# stm32f072.net
KiCad netlist of a schematic drawn in EAGLE
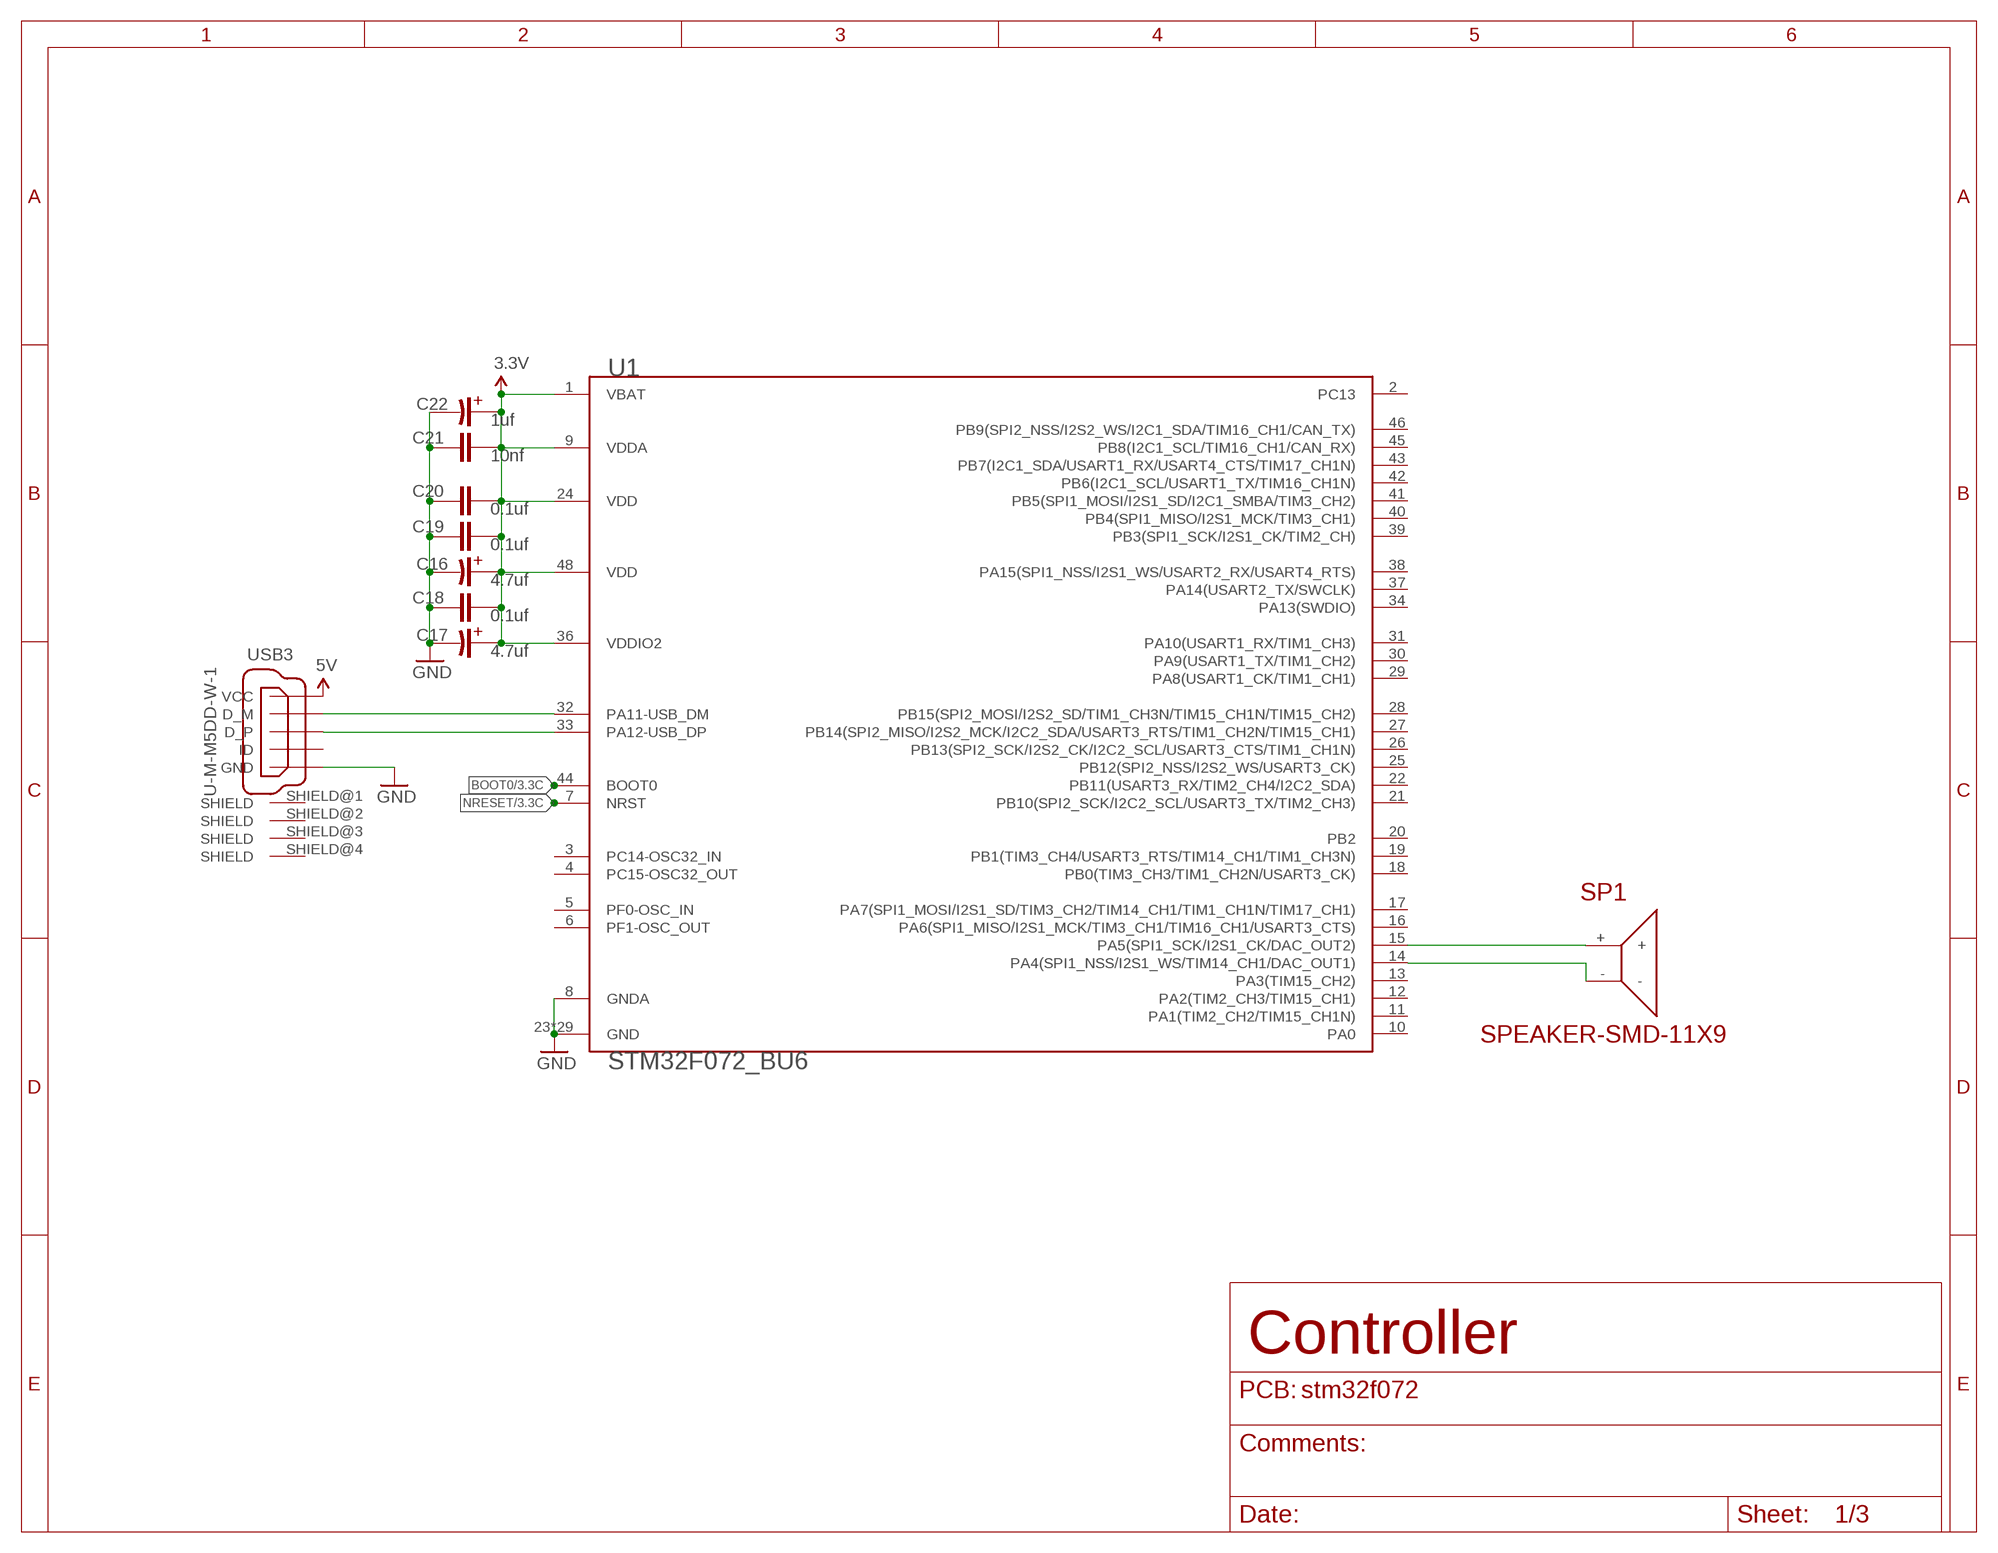
[diagram p0: schematic, sheet 1]
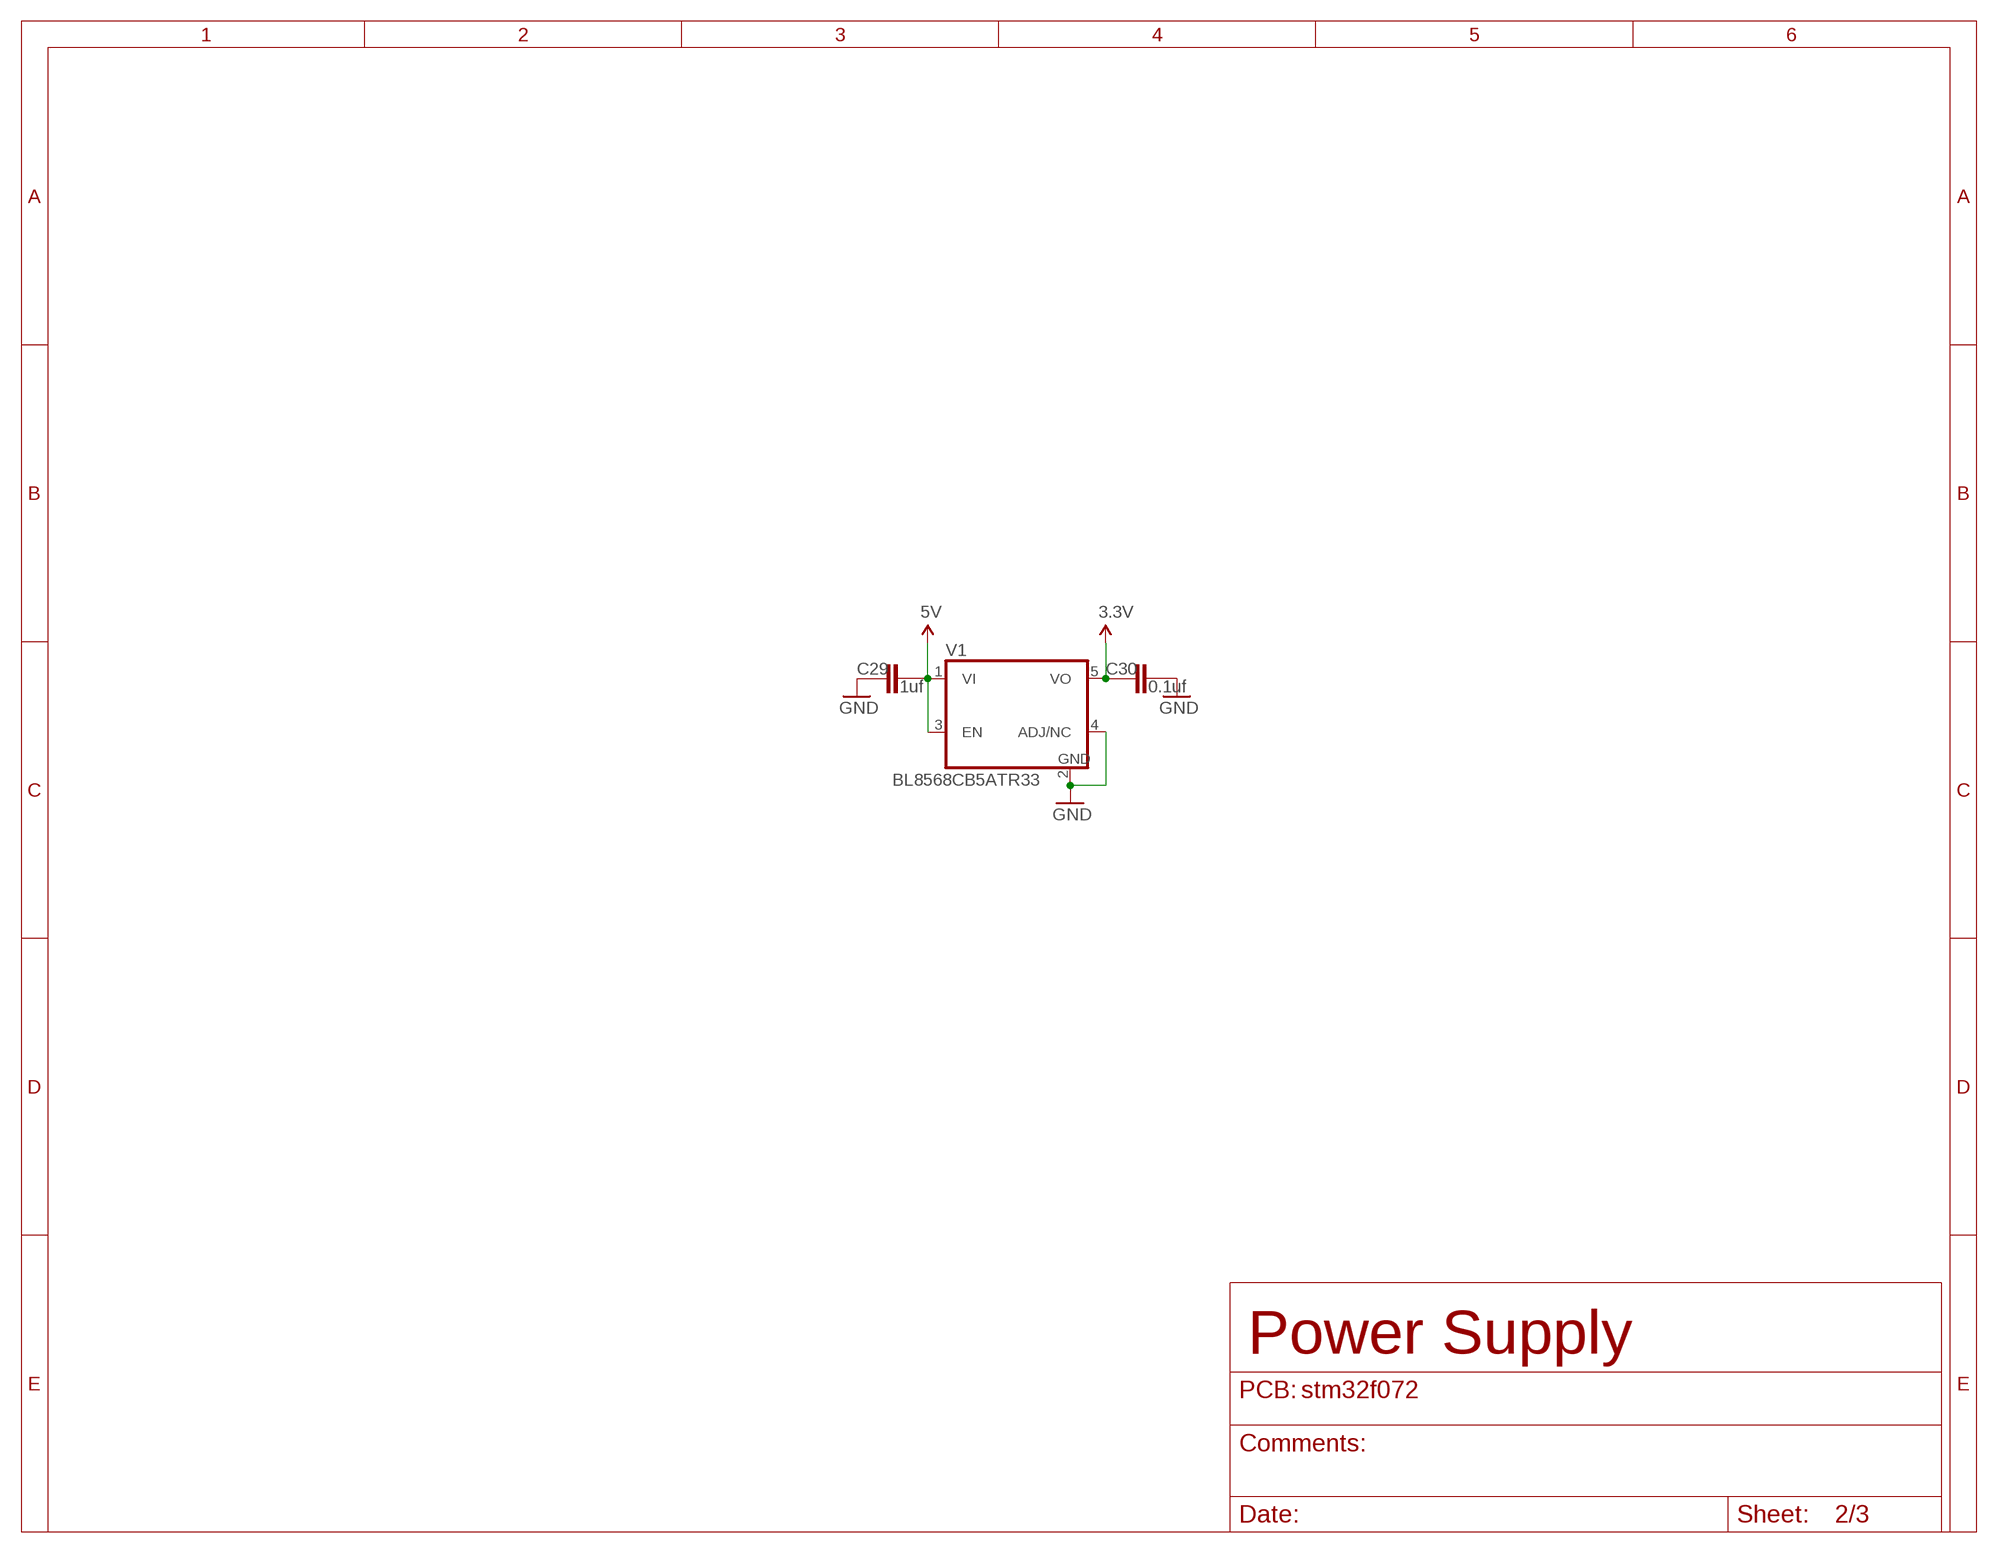
[diagram p1: schematic, sheet 2]
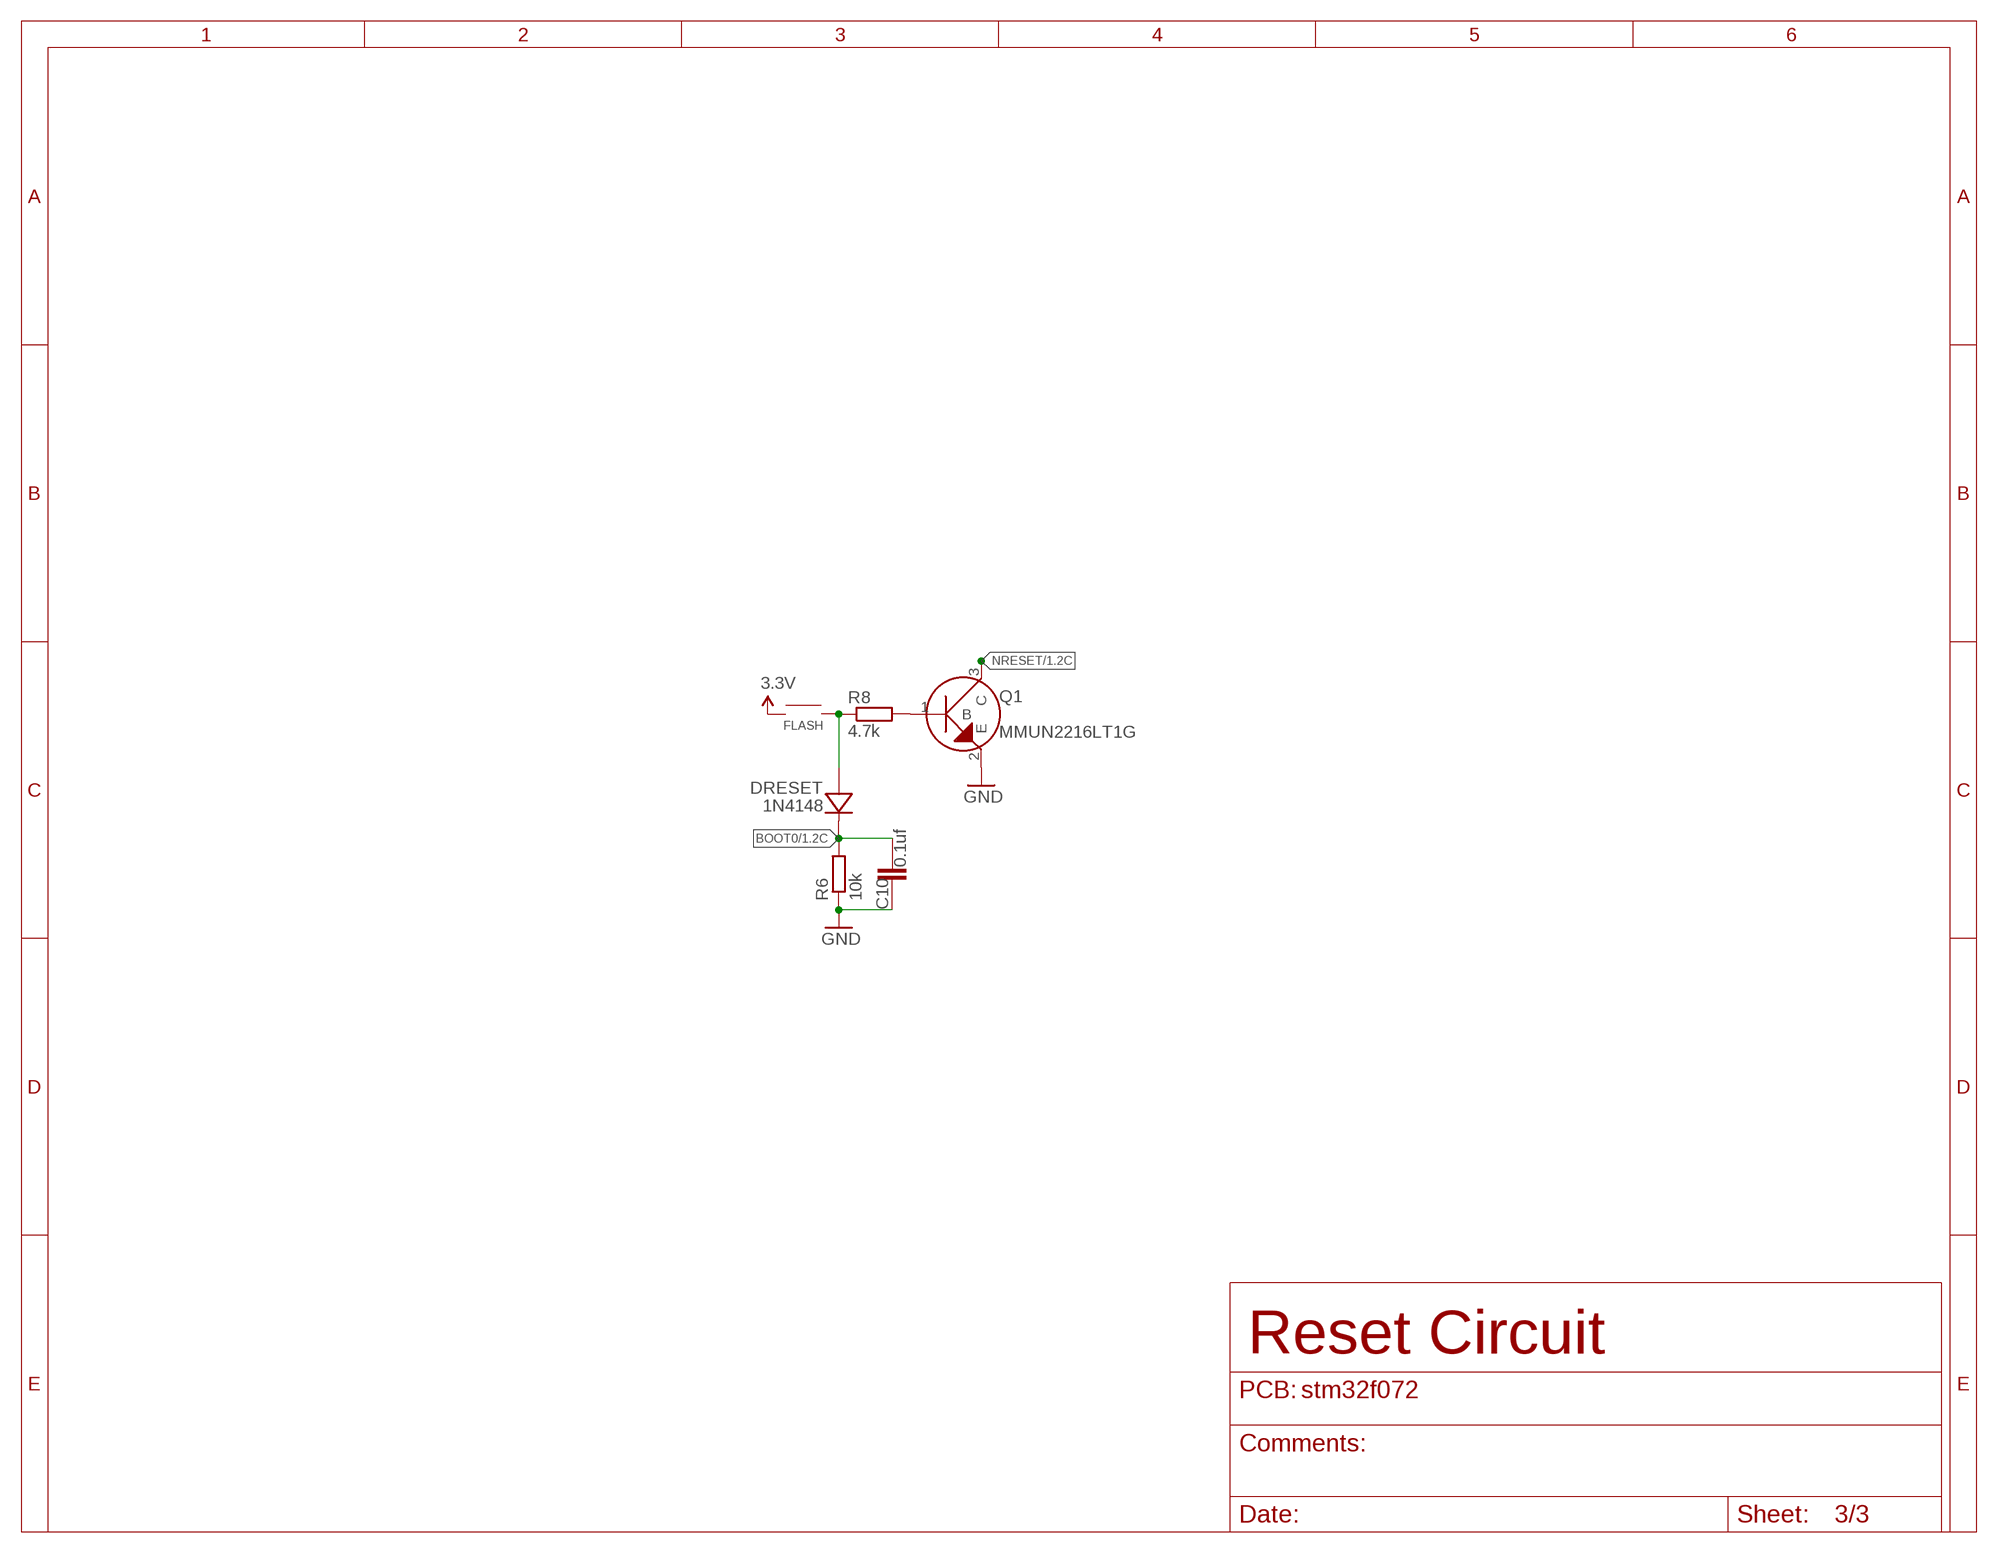
[diagram p2: schematic, sheet 3]

(export (version "E")
  (design (tool "Eeschema 10.0.6"))
  (components
    (comp (ref "C16")
      (value "4.7uf")
      (footprint "eagle-import:C0805-TANT")
      (libsource (lib "eagle-import") (part "CAPACITOR-TANT-0805"))
    )
    (comp (ref "C17")
      (value "4.7uf")
      (footprint "eagle-import:C0805-TANT")
      (libsource (lib "eagle-import") (part "CAPACITOR-TANT-0805"))
    )
    (comp (ref "C18")
      (value "0.1uf")
      (footprint "eagle-import:C0402")
      (libsource (lib "eagle-import") (part "CAPACITOR-0402"))
    )
    (comp (ref "C19")
      (value "0.1uf")
      (footprint "eagle-import:C0402")
      (libsource (lib "eagle-import") (part "CAPACITOR-0402"))
    )
    (comp (ref "C20")
      (value "0.1uf")
      (footprint "eagle-import:C0402")
      (libsource (lib "eagle-import") (part "CAPACITOR-0402"))
    )
    (comp (ref "C21")
      (value "10nf")
      (footprint "eagle-import:C0402")
      (libsource (lib "eagle-import") (part "CAPACITOR-0402"))
    )
    (comp (ref "C22")
      (value "1uf")
      (footprint "eagle-import:C0805-TANT")
      (libsource (lib "eagle-import") (part "CAPACITOR-TANT-0805"))
    )
    (comp (ref "SP1")
      (value "SPEAKER-SMD-11X9")
      (footprint "eagle-import:AST1109MLTRQ")
      (libsource (lib "eagle-import") (part "SPEAKER-SMD-11X9"))
    )
    (comp (ref "U1")
      (value "STM32F072_BU6")
      (footprint "eagle-import:UFQFPN-48")
      (libsource (lib "eagle-import") (part "STM32F072_BU6"))
    )
    (comp (ref "USB3")
      (value "U-M-M5DD-W-1")
      (footprint "eagle-import:U-M-M5DD-W-1")
      (libsource (lib "eagle-import") (part "USB_CONN-LCSC"))
    )
    (comp (ref "C29")
      (value "1uf")
      (footprint "eagle-import:C0402")
      (libsource (lib "eagle-import") (part "CAPACITOR-0402"))
    )
    (comp (ref "C30")
      (value "0.1uf")
      (footprint "eagle-import:C0402")
      (libsource (lib "eagle-import") (part "CAPACITOR-0402"))
    )
    (comp (ref "V1")
      (value "BL8568CB5ATR33")
      (footprint "eagle-import:SOT-23-5")
      (libsource (lib "eagle-import") (part "LDO-VR"))
    )
    (comp (ref "C10")
      (value "0.1uf")
      (footprint "eagle-import:C0402")
      (libsource (lib "eagle-import") (part "CAPACITOR-0402"))
    )
    (comp (ref "DRESET")
      (value "1N4148")
      (footprint "eagle-import:SOD-123")
      (libsource (lib "eagle-import") (part "DIODE-SOD-123"))
    )
    (comp (ref "FLASH")
      (value "SKRPABE010")
      (footprint "eagle-import:SWITCH-SMD-SKRPABE010")
      (libsource (lib "eagle-import") (part "SWITCH-SMD-SKRPABE010"))
    )
    (comp (ref "Q1")
      (value "MMUN2216LT1G")
      (footprint "eagle-import:SOT-23-3")
      (libsource (lib "eagle-import") (part "TRANSISTOR-NPN"))
    )
    (comp (ref "R6")
      (value "10k")
      (footprint "eagle-import:R0402")
      (libsource (lib "eagle-import") (part "RESISTOR-0405"))
    )
    (comp (ref "R8")
      (value "4.7k")
      (footprint "eagle-import:R0402")
      (libsource (lib "eagle-import") (part "RESISTOR-0405"))
    )
  )
  (nets
    (net (code "1") (name "3.3V") (class "Default")
      (node (ref "C16") (pin "1") (pinfunction "+_1") (pintype "passive"))
      (node (ref "C17") (pin "1") (pinfunction "+_1") (pintype "passive"))
      (node (ref "C18") (pin "2") (pinfunction "2_2") (pintype "passive"))
      (node (ref "C19") (pin "2") (pinfunction "2_2") (pintype "passive"))
      (node (ref "C20") (pin "2") (pinfunction "2_2") (pintype "passive"))
      (node (ref "C21") (pin "2") (pinfunction "2_2") (pintype "passive"))
      (node (ref "C22") (pin "1") (pinfunction "+_1") (pintype "passive"))
      (node (ref "C30") (pin "1") (pinfunction "1_1") (pintype "passive"))
      (node (ref "FLASH") (pin "1A") (pinfunction "1_1A") (pintype "passive"))
      (node (ref "FLASH") (pin "1B") (pinfunction "1_1B") (pintype "passive"))
      (node (ref "U1") (pin "1") (pinfunction "VBAT_1") (pintype "bidirectional"))
      (node (ref "U1") (pin "24") (pinfunction "VDD_24") (pintype "bidirectional"))
      (node (ref "U1") (pin "36") (pinfunction "VDDIO2_36") (pintype "bidirectional"))
      (node (ref "U1") (pin "48") (pinfunction "VDD_48") (pintype "bidirectional"))
      (node (ref "U1") (pin "9") (pinfunction "VDDA_9") (pintype "bidirectional"))
      (node (ref "V1") (pin "5") (pinfunction "VO_5") (pintype "passive"))
    )
    (net (code "2") (name "5V") (class "Default")
      (node (ref "C29") (pin "2") (pinfunction "2_2") (pintype "passive"))
      (node (ref "USB3") (pin "VCC") (pinfunction "VCC_VCC") (pintype "input"))
      (node (ref "V1") (pin "1") (pinfunction "VI_1") (pintype "input"))
      (node (ref "V1") (pin "3") (pinfunction "EN_3") (pintype "input"))
    )
    (net (code "3") (name "BOOT0") (class "Default")
      (node (ref "C10") (pin "2") (pinfunction "2_2") (pintype "passive"))
      (node (ref "DRESET") (pin "C") (pinfunction "C_C") (pintype "passive"))
      (node (ref "R6") (pin "2") (pinfunction "2_2") (pintype "passive"))
      (node (ref "U1") (pin "44") (pinfunction "BOOT0_44") (pintype "bidirectional"))
    )
    (net (code "4") (name "GND") (class "Default")
      (node (ref "C10") (pin "1") (pinfunction "1_1") (pintype "passive"))
      (node (ref "C16") (pin "2") (pinfunction "-_2") (pintype "passive"))
      (node (ref "C17") (pin "2") (pinfunction "-_2") (pintype "passive"))
      (node (ref "C18") (pin "1") (pinfunction "1_1") (pintype "passive"))
      (node (ref "C19") (pin "1") (pinfunction "1_1") (pintype "passive"))
      (node (ref "C20") (pin "1") (pinfunction "1_1") (pintype "passive"))
      (node (ref "C21") (pin "1") (pinfunction "1_1") (pintype "passive"))
      (node (ref "C22") (pin "2") (pinfunction "-_2") (pintype "passive"))
      (node (ref "C29") (pin "1") (pinfunction "1_1") (pintype "passive"))
      (node (ref "C30") (pin "2") (pinfunction "2_2") (pintype "passive"))
      (node (ref "Q1") (pin "2") (pinfunction "E_2") (pintype "bidirectional"))
      (node (ref "R6") (pin "1") (pinfunction "1_1") (pintype "passive"))
      (node (ref "U1") (pin "23") (pinfunction "GND_23") (pintype "bidirectional"))
      (node (ref "U1") (pin "35") (pinfunction "GND_35") (pintype "bidirectional"))
      (node (ref "U1") (pin "47") (pinfunction "GND_47") (pintype "bidirectional"))
      (node (ref "U1") (pin "8") (pinfunction "GNDA_8") (pintype "bidirectional"))
      (node (ref "U1") (pin "P$1") (pinfunction "GND_P$1") (pintype "bidirectional"))
      (node (ref "U1") (pin "P$10") (pinfunction "GND_P$10") (pintype "bidirectional"))
      (node (ref "U1") (pin "P$11") (pinfunction "GND_P$11") (pintype "bidirectional"))
      (node (ref "U1") (pin "P$12") (pinfunction "GND_P$12") (pintype "bidirectional"))
      (node (ref "U1") (pin "P$13") (pinfunction "GND_P$13") (pintype "bidirectional"))
      (node (ref "U1") (pin "P$14") (pinfunction "GND_P$14") (pintype "bidirectional"))
      (node (ref "U1") (pin "P$15") (pinfunction "GND_P$15") (pintype "bidirectional"))
      (node (ref "U1") (pin "P$16") (pinfunction "GND_P$16") (pintype "bidirectional"))
      (node (ref "U1") (pin "P$17") (pinfunction "GND_P$17") (pintype "bidirectional"))
      (node (ref "U1") (pin "P$18") (pinfunction "GND_P$18") (pintype "bidirectional"))
      (node (ref "U1") (pin "P$19") (pinfunction "GND_P$19") (pintype "bidirectional"))
      (node (ref "U1") (pin "P$2") (pinfunction "GND_P$2") (pintype "bidirectional"))
      (node (ref "U1") (pin "P$20") (pinfunction "GND_P$20") (pintype "bidirectional"))
      (node (ref "U1") (pin "P$21") (pinfunction "GND_P$21") (pintype "bidirectional"))
      (node (ref "U1") (pin "P$22") (pinfunction "GND_P$22") (pintype "bidirectional"))
      (node (ref "U1") (pin "P$23") (pinfunction "GND_P$23") (pintype "bidirectional"))
      (node (ref "U1") (pin "P$24") (pinfunction "GND_P$24") (pintype "bidirectional"))
      (node (ref "U1") (pin "P$25") (pinfunction "GND_P$25") (pintype "bidirectional"))
      (node (ref "U1") (pin "P$3") (pinfunction "GND_P$3") (pintype "bidirectional"))
      (node (ref "U1") (pin "P$4") (pinfunction "GND_P$4") (pintype "bidirectional"))
      (node (ref "U1") (pin "P$5") (pinfunction "GND_P$5") (pintype "bidirectional"))
      (node (ref "U1") (pin "P$6") (pinfunction "GND_P$6") (pintype "bidirectional"))
      (node (ref "U1") (pin "P$7") (pinfunction "GND_P$7") (pintype "bidirectional"))
      (node (ref "U1") (pin "P$8") (pinfunction "GND_P$8") (pintype "bidirectional"))
      (node (ref "U1") (pin "P$9") (pinfunction "GND_P$9") (pintype "bidirectional"))
      (node (ref "U1") (pin "PAD") (pinfunction "GND_PAD") (pintype "bidirectional"))
      (node (ref "USB3") (pin "GND") (pinfunction "GND_GND") (pintype "input"))
      (node (ref "V1") (pin "2") (pinfunction "GND_2") (pintype "passive"))
      (node (ref "V1") (pin "4") (pinfunction "ADJ/NC_4") (pintype "passive"))
    )
    (net (code "5") (name "NRESET") (class "Default")
      (node (ref "Q1") (pin "3") (pinfunction "C_3") (pintype "bidirectional"))
      (node (ref "U1") (pin "7") (pinfunction "NRST_7") (pintype "bidirectional"))
    )
    (net (code "6") (name "Net-(DRESET-PadA)") (class "Default")
      (node (ref "DRESET") (pin "A") (pinfunction "A_A") (pintype "passive"))
      (node (ref "FLASH") (pin "2A") (pinfunction "2_2A") (pintype "passive"))
      (node (ref "FLASH") (pin "2B") (pinfunction "2_2B") (pintype "passive"))
      (node (ref "R8") (pin "1") (pinfunction "1_1") (pintype "passive"))
    )
    (net (code "7") (name "Net-(Q1-B)") (class "Default")
      (node (ref "Q1") (pin "1") (pinfunction "B_1") (pintype "bidirectional"))
      (node (ref "R8") (pin "2") (pinfunction "2_2") (pintype "passive"))
    )
    (net (code "8") (name "Net-(U1-PA4(SPI1_NSS{slash}I2S1_WS{slash}TIM14_CH1{slash}DAC_OUT1))") (class "Default")
      (node (ref "SP1") (pin "-") (pinfunction "-_-") (pintype "bidirectional"))
      (node (ref "U1") (pin "14") (pinfunction "PA4(SPI1_NSS/I2S1_WS/TIM14_CH1/DAC_OUT1)_14") (pintype "bidirectional"))
    )
    (net (code "9") (name "Net-(U1-PA5(SPI1_SCK{slash}I2S1_CK{slash}DAC_OUT2))") (class "Default")
      (node (ref "SP1") (pin "+") (pinfunction "+_+") (pintype "bidirectional"))
      (node (ref "U1") (pin "15") (pinfunction "PA5(SPI1_SCK/I2S1_CK/DAC_OUT2)_15") (pintype "bidirectional"))
    )
    (net (code "10") (name "Net-(U1-PA11-USB_DM)") (class "Default")
      (node (ref "U1") (pin "32") (pinfunction "PA11-USB_DM_32") (pintype "bidirectional"))
      (node (ref "USB3") (pin "D-") (pinfunction "D_M_D-") (pintype "input"))
    )
    (net (code "11") (name "Net-(U1-PA12-USB_DP)") (class "Default")
      (node (ref "U1") (pin "33") (pinfunction "PA12-USB_DP_33") (pintype "bidirectional"))
      (node (ref "USB3") (pin "D+") (pinfunction "D_P_D+") (pintype "input"))
    )
    (net (code "12") (name "unconnected-(U1-PA0-Pad10)") (class "Default")
      (node (ref "U1") (pin "10") (pinfunction "PA0_10") (pintype "bidirectional"))
    )
    (net (code "13") (name "unconnected-(U1-PA1(TIM2_CH2{slash}TIM15_CH1N)-Pad11)") (class "Default")
      (node (ref "U1") (pin "11") (pinfunction "PA1(TIM2_CH2/TIM15_CH1N)_11") (pintype "bidirectional"))
    )
    (net (code "14") (name "unconnected-(U1-PA2(TIM2_CH3{slash}TIM15_CH1)-Pad12)") (class "Default")
      (node (ref "U1") (pin "12") (pinfunction "PA2(TIM2_CH3/TIM15_CH1)_12") (pintype "bidirectional"))
    )
    (net (code "15") (name "unconnected-(U1-PA3(TIM15_CH2)-Pad13)") (class "Default")
      (node (ref "U1") (pin "13") (pinfunction "PA3(TIM15_CH2)_13") (pintype "bidirectional"))
    )
    (net (code "16") (name "unconnected-(U1-PA6(SPI1_MISO{slash}I2S1_MCK{slash}TIM3_CH1{slash}TIM16_CH1{slash}USART3_CTS)-Pad16)") (class "Default")
      (node (ref "U1") (pin "16") (pinfunction "PA6(SPI1_MISO/I2S1_MCK/TIM3_CH1/TIM16_CH1/USART3_CTS)_16") (pintype "bidirectional"))
    )
    (net (code "17") (name "unconnected-(U1-PA7(SPI1_MOSI{slash}I2S1_SD{slash}TIM3_CH2{slash}TIM14_CH1{slash}TIM1_CH1N{slash}TIM17_CH1)-Pad17)") (class "Default")
      (node (ref "U1") (pin "17") (pinfunction "PA7(SPI1_MOSI/I2S1_SD/TIM3_CH2/TIM14_CH1/TIM1_CH1N/TIM17_CH1)_17") (pintype "bidirectional"))
    )
    (net (code "18") (name "unconnected-(U1-PA8(USART1_CK{slash}TIM1_CH1)-Pad29)") (class "Default")
      (node (ref "U1") (pin "29") (pinfunction "PA8(USART1_CK/TIM1_CH1)_29") (pintype "bidirectional"))
    )
    (net (code "19") (name "unconnected-(U1-PA9(USART1_TX{slash}TIM1_CH2)-Pad30)") (class "Default")
      (node (ref "U1") (pin "30") (pinfunction "PA9(USART1_TX/TIM1_CH2)_30") (pintype "bidirectional"))
    )
    (net (code "20") (name "unconnected-(U1-PA10(USART1_RX{slash}TIM1_CH3)-Pad31)") (class "Default")
      (node (ref "U1") (pin "31") (pinfunction "PA10(USART1_RX/TIM1_CH3)_31") (pintype "bidirectional"))
    )
    (net (code "21") (name "unconnected-(U1-PA13(SWDIO)-Pad34)") (class "Default")
      (node (ref "U1") (pin "34") (pinfunction "PA13(SWDIO)_34") (pintype "bidirectional"))
    )
    (net (code "22") (name "unconnected-(U1-PA14(USART2_TX{slash}SWCLK)-Pad37)") (class "Default")
      (node (ref "U1") (pin "37") (pinfunction "PA14(USART2_TX/SWCLK)_37") (pintype "bidirectional"))
    )
    (net (code "23") (name "unconnected-(U1-PA15(SPI1_NSS{slash}I2S1_WS{slash}USART2_RX{slash}USART4_RTS)-Pad38)") (class "Default")
      (node (ref "U1") (pin "38") (pinfunction "PA15(SPI1_NSS/I2S1_WS/USART2_RX/USART4_RTS)_38") (pintype "bidirectional"))
    )
    (net (code "24") (name "unconnected-(U1-PB0(TIM3_CH3{slash}TIM1_CH2N{slash}USART3_CK)-Pad18)") (class "Default")
      (node (ref "U1") (pin "18") (pinfunction "PB0(TIM3_CH3/TIM1_CH2N/USART3_CK)_18") (pintype "bidirectional"))
    )
    (net (code "25") (name "unconnected-(U1-PB1(TIM3_CH4{slash}USART3_RTS{slash}TIM14_CH1{slash}TIM1_CH3N)-Pad19)") (class "Default")
      (node (ref "U1") (pin "19") (pinfunction "PB1(TIM3_CH4/USART3_RTS/TIM14_CH1/TIM1_CH3N)_19") (pintype "bidirectional"))
    )
    (net (code "26") (name "unconnected-(U1-PB2-Pad20)") (class "Default")
      (node (ref "U1") (pin "20") (pinfunction "PB2_20") (pintype "bidirectional"))
    )
    (net (code "27") (name "unconnected-(U1-PB3(SPI1_SCK{slash}I2S1_CK{slash}TIM2_CH)-Pad39)") (class "Default")
      (node (ref "U1") (pin "39") (pinfunction "PB3(SPI1_SCK/I2S1_CK/TIM2_CH)_39") (pintype "bidirectional"))
    )
    (net (code "28") (name "unconnected-(U1-PB4(SPI1_MISO{slash}I2S1_MCK{slash}TIM3_CH1)-Pad40)") (class "Default")
      (node (ref "U1") (pin "40") (pinfunction "PB4(SPI1_MISO/I2S1_MCK/TIM3_CH1)_40") (pintype "bidirectional"))
    )
    (net (code "29") (name "unconnected-(U1-PB5(SPI1_MOSI{slash}I2S1_SD{slash}I2C1_SMBA{slash}TIM3_CH2)-Pad41)") (class "Default")
      (node (ref "U1") (pin "41") (pinfunction "PB5(SPI1_MOSI/I2S1_SD/I2C1_SMBA/TIM3_CH2)_41") (pintype "bidirectional"))
    )
    (net (code "30") (name "unconnected-(U1-PB6(I2C1_SCL{slash}USART1_TX{slash}TIM16_CH1N)-Pad42)") (class "Default")
      (node (ref "U1") (pin "42") (pinfunction "PB6(I2C1_SCL/USART1_TX/TIM16_CH1N)_42") (pintype "bidirectional"))
    )
    (net (code "31") (name "unconnected-(U1-PB7(I2C1_SDA{slash}USART1_RX{slash}USART4_CTS{slash}TIM17_CH1N)-Pad43)") (class "Default")
      (node (ref "U1") (pin "43") (pinfunction "PB7(I2C1_SDA/USART1_RX/USART4_CTS/TIM17_CH1N)_43") (pintype "bidirectional"))
    )
    (net (code "32") (name "unconnected-(U1-PB8(I2C1_SCL{slash}TIM16_CH1{slash}CAN_RX)-Pad45)") (class "Default")
      (node (ref "U1") (pin "45") (pinfunction "PB8(I2C1_SCL/TIM16_CH1/CAN_RX)_45") (pintype "bidirectional"))
    )
    (net (code "33") (name "unconnected-(U1-PB9(SPI2_NSS{slash}I2S2_WS{slash}I2C1_SDA{slash}TIM16_CH1{slash}CAN_TX)-Pad46)") (class "Default")
      (node (ref "U1") (pin "46") (pinfunction "PB9(SPI2_NSS/I2S2_WS/I2C1_SDA/TIM16_CH1/CAN_TX)_46") (pintype "bidirectional"))
    )
    (net (code "34") (name "unconnected-(U1-PB10(SPI2_SCK{slash}I2C2_SCL{slash}USART3_TX{slash}TIM2_CH3)-Pad21)") (class "Default")
      (node (ref "U1") (pin "21") (pinfunction "PB10(SPI2_SCK/I2C2_SCL/USART3_TX/TIM2_CH3)_21") (pintype "bidirectional"))
    )
    (net (code "35") (name "unconnected-(U1-PB11(USART3_RX{slash}TIM2_CH4{slash}I2C2_SDA)-Pad22)") (class "Default")
      (node (ref "U1") (pin "22") (pinfunction "PB11(USART3_RX/TIM2_CH4/I2C2_SDA)_22") (pintype "bidirectional"))
    )
    (net (code "36") (name "unconnected-(U1-PB12(SPI2_NSS{slash}I2S2_WS{slash}USART3_CK)-Pad25)") (class "Default")
      (node (ref "U1") (pin "25") (pinfunction "PB12(SPI2_NSS/I2S2_WS/USART3_CK)_25") (pintype "bidirectional"))
    )
    (net (code "37") (name "unconnected-(U1-PB13(SPI2_SCK{slash}I2S2_CK{slash}I2C2_SCL{slash}USART3_CTS{slash}TIM1_CH1N)-Pad26)") (class "Default")
      (node (ref "U1") (pin "26") (pinfunction "PB13(SPI2_SCK/I2S2_CK/I2C2_SCL/USART3_CTS/TIM1_CH1N)_26") (pintype "bidirectional"))
    )
    (net (code "38") (name "unconnected-(U1-PB14(SPI2_MISO{slash}I2S2_MCK{slash}I2C2_SDA{slash}USART3_RTS{slash}TIM1_CH2N{slash}TIM15_CH1)-Pad27)") (class "Default")
      (node (ref "U1") (pin "27") (pinfunction "PB14(SPI2_MISO/I2S2_MCK/I2C2_SDA/USART3_RTS/TIM1_CH2N/TIM15_CH1)_27") (pintype "bidirectional"))
    )
    (net (code "39") (name "unconnected-(U1-PB15(SPI2_MOSI{slash}I2S2_SD{slash}TIM1_CH3N{slash}TIM15_CH1N{slash}TIM15_CH2)-Pad28)") (class "Default")
      (node (ref "U1") (pin "28") (pinfunction "PB15(SPI2_MOSI/I2S2_SD/TIM1_CH3N/TIM15_CH1N/TIM15_CH2)_28") (pintype "bidirectional"))
    )
    (net (code "40") (name "unconnected-(U1-PC13-Pad2)") (class "Default")
      (node (ref "U1") (pin "2") (pinfunction "PC13_2") (pintype "bidirectional"))
    )
    (net (code "41") (name "unconnected-(U1-PC14-OSC32_IN-Pad3)") (class "Default")
      (node (ref "U1") (pin "3") (pinfunction "PC14-OSC32_IN_3") (pintype "bidirectional"))
    )
    (net (code "42") (name "unconnected-(U1-PC15-OSC32_OUT-Pad4)") (class "Default")
      (node (ref "U1") (pin "4") (pinfunction "PC15-OSC32_OUT_4") (pintype "bidirectional"))
    )
    (net (code "43") (name "unconnected-(U1-PF0-OSC_IN-Pad5)") (class "Default")
      (node (ref "U1") (pin "5") (pinfunction "PF0-OSC_IN_5") (pintype "bidirectional"))
    )
    (net (code "44") (name "unconnected-(U1-PF1-OSC_OUT-Pad6)") (class "Default")
      (node (ref "U1") (pin "6") (pinfunction "PF1-OSC_OUT_6") (pintype "bidirectional"))
    )
    (net (code "45") (name "unconnected-(USB3-PadID)") (class "Default")
      (node (ref "USB3") (pin "ID") (pinfunction "ID_ID") (pintype "input"))
    )
    (net (code "46") (name "unconnected-(USB3-SHIELD-PadSHIELD@1)") (class "Default")
      (node (ref "USB3") (pin "SHIELD@1") (pinfunction "SHIELD_SHIELD@1") (pintype "bidirectional"))
    )
    (net (code "47") (name "unconnected-(USB3-SHIELD-PadSHIELD@2)") (class "Default")
      (node (ref "USB3") (pin "SHIELD@2") (pinfunction "SHIELD_SHIELD@2") (pintype "bidirectional"))
    )
    (net (code "48") (name "unconnected-(USB3-SHIELD-PadSHIELD@3)") (class "Default")
      (node (ref "USB3") (pin "SHIELD@3") (pinfunction "SHIELD_SHIELD@3") (pintype "bidirectional"))
    )
    (net (code "49") (name "unconnected-(USB3-SHIELD-PadSHIELD@4)") (class "Default")
      (node (ref "USB3") (pin "SHIELD@4") (pinfunction "SHIELD_SHIELD@4") (pintype "bidirectional"))
    )
  )
)
